# FruitBox_LED.net
KiCad netlist of a schematic drawn in Altium Designer
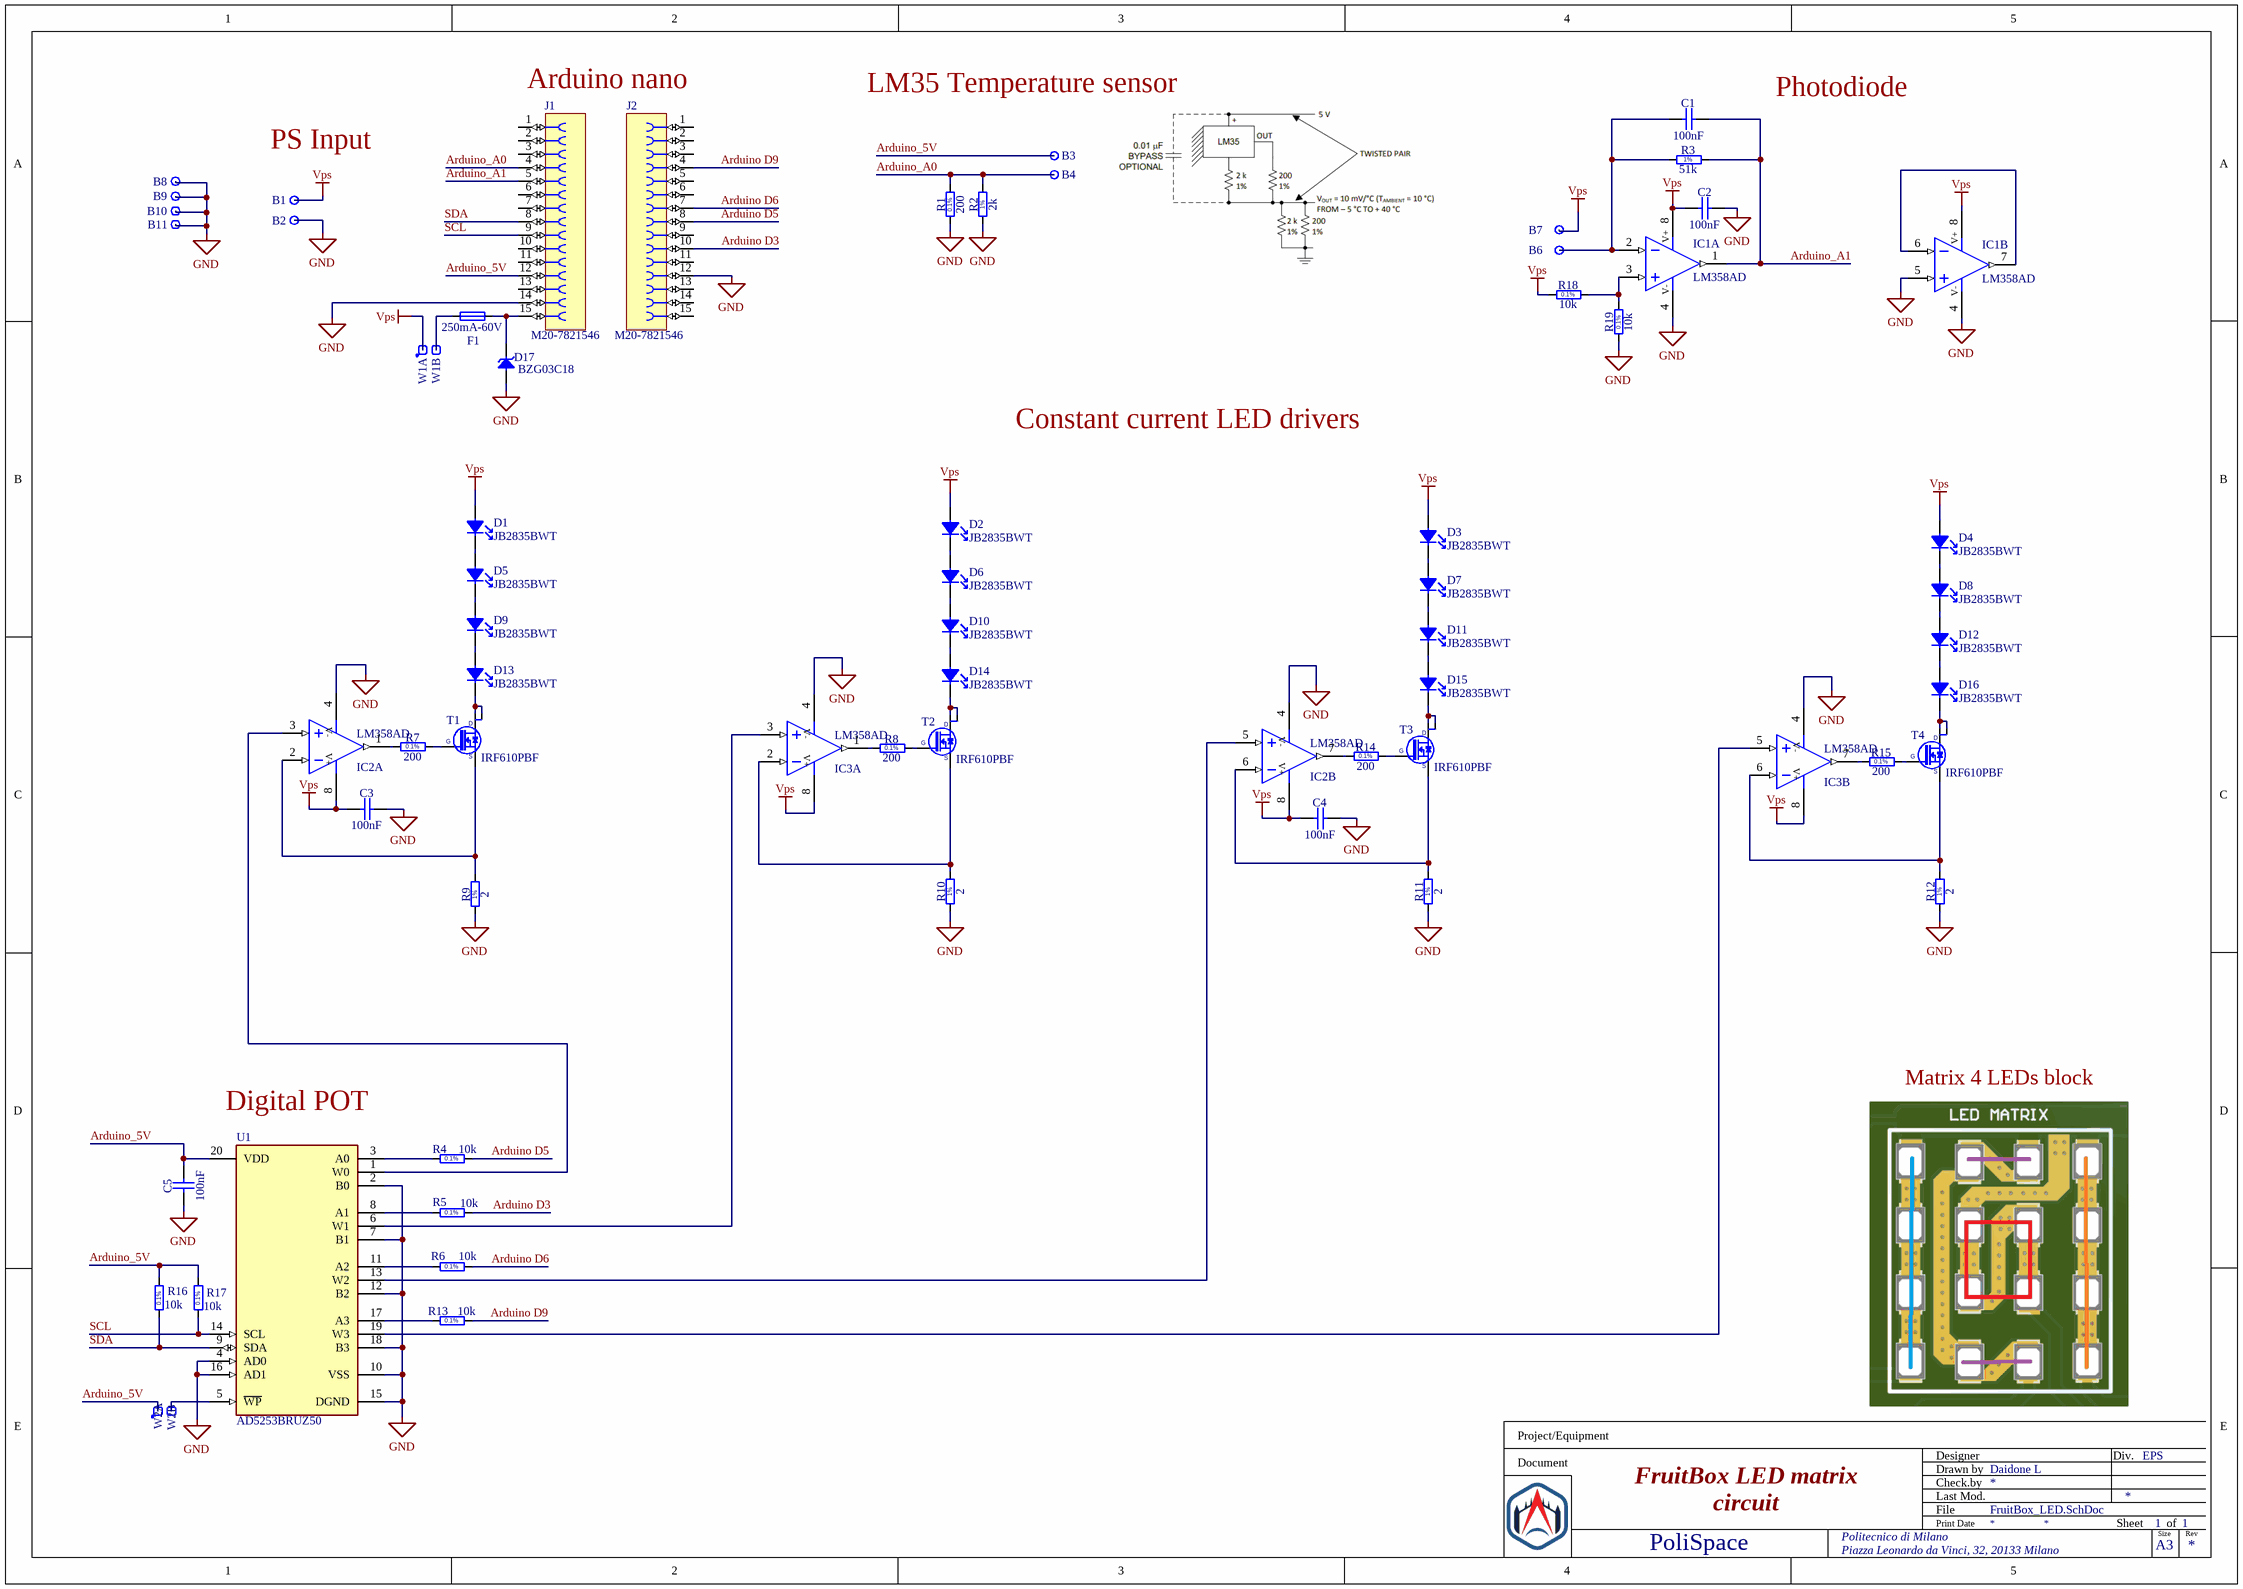
[diagram p0: FruitBox_LED.SchDoc]

(export (version "E")
  (design (tool "Eeschema 10.0.6"))
  (components
    (comp (ref "B1")
      (value "Banana")
      (footprint "CINCH_105-2202-201")
      (description "Single Terminal Socket")
      (fields
        (field (name "PART NUMBER") "CINCH_105-2202-201")
        (field (name "MANUFACTURER") "CINCH CONNECTIVITY")
        (field (name "AUTHOR") "CERN DEM MR")
      )
      (libsource (lib "Connectors") (part "Single Terminal Socket"))
    )
    (comp (ref "B2")
      (value "Banana")
      (footprint "CINCH_105-2203-201")
      (description "Single Terminal Socket")
      (fields
        (field (name "PART NUMBER") "CINCH_105-2203-201")
        (field (name "MANUFACTURER") "CINCH CONNECTIVITY")
        (field (name "AUTHOR") "CERN DEM MR")
      )
      (libsource (lib "Connectors") (part "Single Terminal Socket"))
    )
    (comp (ref "B3")
      (value "Plated Hole")
      (footprint "c130h80")
      (description "Single Terminal Socket")
      (fields (field (name "PART NUMBER") "PLATED_HOLE0.8_PAD1.3") (field (name "AUTHOR") "CERN DEM JLC"))
      (libsource (lib "Eletro-mechanical") (part "Single Terminal Socket"))
    )
    (comp (ref "B4")
      (value "Plated Hole")
      (footprint "c130h80")
      (description "Single Terminal Socket")
      (fields (field (name "PART NUMBER") "PLATED_HOLE0.8_PAD1.3") (field (name "AUTHOR") "CERN DEM JLC"))
      (libsource (lib "Eletro-mechanical") (part "Single Terminal Socket"))
    )
    (comp (ref "B6")
      (value "Plated Hole")
      (footprint "c130h80")
      (description "Single Terminal Socket")
      (fields (field (name "PART NUMBER") "PLATED_HOLE0.8_PAD1.3") (field (name "AUTHOR") "CERN DEM JLC"))
      (libsource (lib "Eletro-mechanical") (part "Single Terminal Socket"))
    )
    (comp (ref "B7")
      (value "Plated Hole")
      (footprint "c130h80")
      (description "Single Terminal Socket")
      (fields (field (name "PART NUMBER") "PLATED_HOLE0.8_PAD1.3") (field (name "AUTHOR") "CERN DEM JLC"))
      (libsource (lib "Eletro-mechanical") (part "Single Terminal Socket"))
    )
    (comp (ref "B8")
      (value "Plated Hole")
      (footprint "MTG320_550")
      (description "Single Terminal Socket")
      (fields (field (name "PART NUMBER") "PLATED_HOLE3.2_PAD5.5") (field (name "AUTHOR") "CERN DEM JMW"))
      (libsource (lib "Eletro-mechanical") (part "Single Terminal Socket"))
    )
    (comp (ref "B9")
      (value "Plated Hole")
      (footprint "MTG320_550")
      (description "Single Terminal Socket")
      (fields (field (name "PART NUMBER") "PLATED_HOLE3.2_PAD5.5") (field (name "AUTHOR") "CERN DEM JMW"))
      (libsource (lib "Eletro-mechanical") (part "Single Terminal Socket"))
    )
    (comp (ref "B10")
      (value "Plated Hole")
      (footprint "MTG320_550")
      (description "Single Terminal Socket")
      (fields (field (name "PART NUMBER") "PLATED_HOLE3.2_PAD5.5") (field (name "AUTHOR") "CERN DEM JMW"))
      (libsource (lib "Eletro-mechanical") (part "Single Terminal Socket"))
    )
    (comp (ref "B11")
      (value "Plated Hole")
      (footprint "MTG320_550")
      (description "Single Terminal Socket")
      (fields (field (name "PART NUMBER") "PLATED_HOLE3.2_PAD5.5") (field (name "AUTHOR") "CERN DEM JMW"))
      (libsource (lib "Eletro-mechanical") (part "Single Terminal Socket"))
    )
    (comp (ref "C1")
      (value "100nF")
      (footprint "CAPC1608X87N")
      (description "Non-polarised capacitor")
      (fields
        (field (name "PART NUMBER") "CC0603_100NF_50V_10%_X7R")
        (field (name "VOLTAGE") "50V")
        (field (name "AUTHOR") "CERN DEM JLC")
      )
      (libsource (lib "Capacitors") (part "Capacitor - non polarized"))
    )
    (comp (ref "C2")
      (value "100nF")
      (footprint "CAPC1608X87N")
      (description "Non-polarised capacitor")
      (fields
        (field (name "PART NUMBER") "CC0603_100NF_50V_10%_X7R")
        (field (name "VOLTAGE") "50V")
        (field (name "AUTHOR") "CERN DEM JLC")
      )
      (libsource (lib "Capacitors") (part "Capacitor - non polarized"))
    )
    (comp (ref "C3")
      (value "100nF")
      (footprint "CAPC1608X87N")
      (description "Non-polarised capacitor")
      (fields
        (field (name "PART NUMBER") "CC0603_100NF_50V_10%_X7R")
        (field (name "VOLTAGE") "50V")
        (field (name "AUTHOR") "CERN DEM JLC")
      )
      (libsource (lib "Capacitors") (part "Capacitor - non polarized"))
    )
    (comp (ref "C4")
      (value "100nF")
      (footprint "CAPC1608X87N")
      (description "Non-polarised capacitor")
      (fields
        (field (name "PART NUMBER") "CC0603_100NF_50V_10%_X7R")
        (field (name "VOLTAGE") "50V")
        (field (name "AUTHOR") "CERN DEM JLC")
      )
      (libsource (lib "Capacitors") (part "Capacitor - non polarized"))
    )
    (comp (ref "C5")
      (value "100nF")
      (footprint "CAPC1608X87N")
      (description "Non-polarised capacitor")
      (fields
        (field (name "PART NUMBER") "CC0603_100NF_50V_10%_X7R")
        (field (name "VOLTAGE") "50V")
        (field (name "AUTHOR") "CERN DEM JLC")
      )
      (libsource (lib "Capacitors") (part "Capacitor - non polarized"))
    )
    (comp (ref "D1")
      (value "JB2835BWT")
      (footprint "JB2835BWT")
      (libsource (lib "6SCubeSat") (part "JB2835BWT-G-U35GA0000"))
    )
    (comp (ref "D2")
      (value "JB2835BWT")
      (footprint "JB2835BWT")
      (libsource (lib "6SCubeSat") (part "JB2835BWT-G-U35GA0000"))
    )
    (comp (ref "D3")
      (value "JB2835BWT")
      (footprint "JB2835BWT")
      (libsource (lib "6SCubeSat") (part "JB2835BWT-G-U35GA0000"))
    )
    (comp (ref "D4")
      (value "JB2835BWT")
      (footprint "JB2835BWT")
      (libsource (lib "6SCubeSat") (part "JB2835BWT-G-U35GA0000"))
    )
    (comp (ref "D5")
      (value "JB2835BWT")
      (footprint "JB2835BWT")
      (libsource (lib "6SCubeSat") (part "JB2835BWT-G-U35GA0000"))
    )
    (comp (ref "D6")
      (value "JB2835BWT")
      (footprint "JB2835BWT")
      (libsource (lib "6SCubeSat") (part "JB2835BWT-G-U35GA0000"))
    )
    (comp (ref "D7")
      (value "JB2835BWT")
      (footprint "JB2835BWT")
      (libsource (lib "6SCubeSat") (part "JB2835BWT-G-U35GA0000"))
    )
    (comp (ref "D8")
      (value "JB2835BWT")
      (footprint "JB2835BWT")
      (libsource (lib "6SCubeSat") (part "JB2835BWT-G-U35GA0000"))
    )
    (comp (ref "D9")
      (value "JB2835BWT")
      (footprint "JB2835BWT")
      (libsource (lib "6SCubeSat") (part "JB2835BWT-G-U35GA0000"))
    )
    (comp (ref "D10")
      (value "JB2835BWT")
      (footprint "JB2835BWT")
      (libsource (lib "6SCubeSat") (part "JB2835BWT-G-U35GA0000"))
    )
    (comp (ref "D11")
      (value "JB2835BWT")
      (footprint "JB2835BWT")
      (libsource (lib "6SCubeSat") (part "JB2835BWT-G-U35GA0000"))
    )
    (comp (ref "D12")
      (value "JB2835BWT")
      (footprint "JB2835BWT")
      (libsource (lib "6SCubeSat") (part "JB2835BWT-G-U35GA0000"))
    )
    (comp (ref "D13")
      (value "JB2835BWT")
      (footprint "JB2835BWT")
      (libsource (lib "6SCubeSat") (part "JB2835BWT-G-U35GA0000"))
    )
    (comp (ref "D14")
      (value "JB2835BWT")
      (footprint "JB2835BWT")
      (libsource (lib "6SCubeSat") (part "JB2835BWT-G-U35GA0000"))
    )
    (comp (ref "D15")
      (value "JB2835BWT")
      (footprint "JB2835BWT")
      (libsource (lib "6SCubeSat") (part "JB2835BWT-G-U35GA0000"))
    )
    (comp (ref "D16")
      (value "JB2835BWT")
      (footprint "JB2835BWT")
      (libsource (lib "6SCubeSat") (part "JB2835BWT-G-U35GA0000"))
    )
    (comp (ref "D17")
      (value "BZG03C18")
      (footprint "DIOM5326X230N")
      (description "Zener Diode")
      (fields
        (field (name "VOLTAGE") "18V")
        (field (name "POWER") "1.25W")
        (field (name "AUTHOR") "CERN DEM JLC")
      )
      (libsource (lib "ICs And Semiconductors") (part "Diode Zener"))
    )
    (comp (ref "F1")
      (value "250mA-60V")
      (footprint "FUSR_BEL_0ZCJ0010FF2E")
      (description "Fuse")
      (fields
        (field (name "PART NUMBER") "FUSR1206_BEL_0ZCJ0010FF2E")
        (field (name "MANUFACTURER") "BEL")
        (field (name "AUTHOR") "CERN DEM BR")
      )
      (libsource (lib "Eletro-mechanical") (part "Fuse"))
    )
    (comp (ref "IC1")
      (value "LM358AD")
      (footprint "SOIC127P600X175-8N")
      (description "Dual Operational Amplifier")
      (fields (field (name "MANUFACTURER") "TEXAS INSTRUMENTS") (field (name "AUTHOR") "CERN DEM JLC"))
      (libsource (lib "ICs And Semiconductors") (part "Operational Amplifier x2 Type1"))
    )
    (comp (ref "IC2")
      (value "LM358AD")
      (footprint "SOIC127P600X175-8N")
      (description "Dual Operational Amplifier")
      (fields (field (name "MANUFACTURER") "TEXAS INSTRUMENTS") (field (name "AUTHOR") "CERN DEM JLC"))
      (libsource (lib "ICs And Semiconductors") (part "Operational Amplifier x2 Type1"))
    )
    (comp (ref "IC3")
      (value "LM358AD")
      (footprint "SOIC127P600X175-8N")
      (description "Dual Operational Amplifier")
      (fields (field (name "MANUFACTURER") "TEXAS INSTRUMENTS") (field (name "AUTHOR") "CERN DEM JLC"))
      (libsource (lib "ICs And Semiconductors") (part "Operational Amplifier x2 Type1"))
    )
    (comp (ref "J1")
      (value "M20-7821546")
      (footprint "M20-7821546")
      (libsource (lib "6SCubeSat") (part "M20-7821546"))
    )
    (comp (ref "J2")
      (value "M20-7821546")
      (footprint "M20-7821546")
      (libsource (lib "") (part "M20-7821546_1"))
    )
    (comp (ref "R1")
      (value "200")
      (footprint "RESC1608X64N")
      (description "Resistor - 0.1%")
      (fields
        (field (name "PART NUMBER") "R0603_200R_0.1%_0.1W_25PPM")
        (field (name "POWER") "0.1W")
        (field (name "AUTHOR") "CERN DEM JLC")
      )
      (libsource (lib "Resistors") (part "Resistor - 0.1%"))
    )
    (comp (ref "R2")
      (value "2k")
      (footprint "RESC1608X55N")
      (description "Resistor - 1%")
      (fields
        (field (name "PART NUMBER") "R0603_2K_1%_0.1W_100PPM")
        (field (name "POWER") "0.1W")
        (field (name "AUTHOR") "CERN DEM JLC")
      )
      (libsource (lib "Resistors") (part "Resistor - 1%"))
    )
    (comp (ref "R3")
      (value "51k")
      (footprint "RESC2012X60N")
      (description "Resistor - 1%")
      (fields
        (field (name "PART NUMBER") "R0805_51K_1%_0.125W_100PPM")
        (field (name "POWER") "0.125W")
        (field (name "AUTHOR") "CERN DEM JLC")
      )
      (libsource (lib "Resistors") (part "Resistor - 1%"))
    )
    (comp (ref "R4")
      (value "10k")
      (footprint "RESC1608X64N")
      (description "Resistor - 0.1%")
      (fields
        (field (name "PART NUMBER") "R0603_10K_0.1%_0.1W_25PPM")
        (field (name "POWER") "0.1W")
        (field (name "AUTHOR") "CERN DEM JMW")
      )
      (libsource (lib "Resistors") (part "Resistor - 0.1%"))
    )
    (comp (ref "R5")
      (value "10k")
      (footprint "RESC1608X64N")
      (description "Resistor - 0.1%")
      (fields
        (field (name "PART NUMBER") "R0603_10K_0.1%_0.1W_25PPM")
        (field (name "POWER") "0.1W")
        (field (name "AUTHOR") "CERN DEM JMW")
      )
      (libsource (lib "Resistors") (part "Resistor - 0.1%"))
    )
    (comp (ref "R6")
      (value "10k")
      (footprint "RESC1608X64N")
      (description "Resistor - 0.1%")
      (fields
        (field (name "PART NUMBER") "R0603_10K_0.1%_0.1W_25PPM")
        (field (name "POWER") "0.1W")
        (field (name "AUTHOR") "CERN DEM JMW")
      )
      (libsource (lib "Resistors") (part "Resistor - 0.1%"))
    )
    (comp (ref "R7")
      (value "200")
      (footprint "RESC1608X64N")
      (description "Resistor - 0.1%")
      (fields
        (field (name "PART NUMBER") "R0603_200R_0.1%_0.1W_25PPM")
        (field (name "POWER") "0.1W")
        (field (name "AUTHOR") "CERN DEM JLC")
      )
      (libsource (lib "Resistors") (part "Resistor - 0.1%"))
    )
    (comp (ref "R8")
      (value "200")
      (footprint "RESC1608X64N")
      (description "Resistor - 0.1%")
      (fields
        (field (name "PART NUMBER") "R0603_200R_0.1%_0.1W_25PPM")
        (field (name "POWER") "0.1W")
        (field (name "AUTHOR") "CERN DEM JLC")
      )
      (libsource (lib "Resistors") (part "Resistor - 0.1%"))
    )
    (comp (ref "R9")
      (value "2")
      (footprint "RES1016-630X250")
      (description "Resistor - 1%")
      (fields
        (field (name "PART NUMBER") "RMF_2R_1%_0.6W_50PPM_1016-630X250")
        (field (name "POWER") "0.6W")
        (field (name "AUTHOR") "CERN DEM JLC")
      )
      (libsource (lib "Resistors") (part "Resistor - 1%"))
    )
    (comp (ref "R10")
      (value "2")
      (footprint "RES1016-630X250")
      (description "Resistor - 1%")
      (fields
        (field (name "PART NUMBER") "RMF_2R_1%_0.6W_50PPM_1016-630X250")
        (field (name "POWER") "0.6W")
        (field (name "AUTHOR") "CERN DEM JLC")
      )
      (libsource (lib "Resistors") (part "Resistor - 1%"))
    )
    (comp (ref "R11")
      (value "2")
      (footprint "RES1016-630X250")
      (description "Resistor - 1%")
      (fields
        (field (name "PART NUMBER") "RMF_2R_1%_0.6W_50PPM_1016-630X250")
        (field (name "POWER") "0.6W")
        (field (name "AUTHOR") "CERN DEM JLC")
      )
      (libsource (lib "Resistors") (part "Resistor - 1%"))
    )
    (comp (ref "R12")
      (value "2")
      (footprint "RES1016-630X250")
      (description "Resistor - 1%")
      (fields
        (field (name "PART NUMBER") "RMF_2R_1%_0.6W_50PPM_1016-630X250")
        (field (name "POWER") "0.6W")
        (field (name "AUTHOR") "CERN DEM JLC")
      )
      (libsource (lib "Resistors") (part "Resistor - 1%"))
    )
    (comp (ref "R13")
      (value "10k")
      (footprint "RESC1608X64N")
      (description "Resistor - 0.1%")
      (fields
        (field (name "PART NUMBER") "R0603_10K_0.1%_0.1W_25PPM")
        (field (name "POWER") "0.1W")
        (field (name "AUTHOR") "CERN DEM JMW")
      )
      (libsource (lib "Resistors") (part "Resistor - 0.1%"))
    )
    (comp (ref "R14")
      (value "200")
      (footprint "RESC1608X64N")
      (description "Resistor - 0.1%")
      (fields
        (field (name "PART NUMBER") "R0603_200R_0.1%_0.1W_25PPM")
        (field (name "POWER") "0.1W")
        (field (name "AUTHOR") "CERN DEM JLC")
      )
      (libsource (lib "Resistors") (part "Resistor - 0.1%"))
    )
    (comp (ref "R15")
      (value "200")
      (footprint "RESC1608X64N")
      (description "Resistor - 0.1%")
      (fields
        (field (name "PART NUMBER") "R0603_200R_0.1%_0.1W_25PPM")
        (field (name "POWER") "0.1W")
        (field (name "AUTHOR") "CERN DEM JLC")
      )
      (libsource (lib "Resistors") (part "Resistor - 0.1%"))
    )
    (comp (ref "R16")
      (value "10k")
      (footprint "RESC1608X64N")
      (description "Resistor - 0.1%")
      (fields
        (field (name "PART NUMBER") "R0603_10K_0.1%_0.1W_25PPM")
        (field (name "POWER") "0.1W")
        (field (name "AUTHOR") "CERN DEM JMW")
      )
      (libsource (lib "Resistors") (part "Resistor - 0.1%"))
    )
    (comp (ref "R17")
      (value "10k")
      (footprint "RESC1608X64N")
      (description "Resistor - 0.1%")
      (fields
        (field (name "PART NUMBER") "R0603_10K_0.1%_0.1W_25PPM")
        (field (name "POWER") "0.1W")
        (field (name "AUTHOR") "CERN DEM JMW")
      )
      (libsource (lib "Resistors") (part "Resistor - 0.1%"))
    )
    (comp (ref "R18")
      (value "10k")
      (footprint "RESC1608X64N")
      (description "Resistor - 0.1%")
      (fields
        (field (name "PART NUMBER") "R0603_10K_0.1%_0.1W_25PPM")
        (field (name "POWER") "0.1W")
        (field (name "AUTHOR") "CERN DEM JMW")
      )
      (libsource (lib "Resistors") (part "Resistor - 0.1%"))
    )
    (comp (ref "R19")
      (value "10k")
      (footprint "RESC1608X64N")
      (description "Resistor - 0.1%")
      (fields
        (field (name "PART NUMBER") "R0603_10K_0.1%_0.1W_25PPM")
        (field (name "POWER") "0.1W")
        (field (name "AUTHOR") "CERN DEM JMW")
      )
      (libsource (lib "Resistors") (part "Resistor - 0.1%"))
    )
    (comp (ref "T1")
      (value "IRF610PBF")
      (footprint "TO-220-H")
      (description "N-CHANNEL MOSFET WITH DIODE AND 2 DRAIN")
      (fields
        (field (name "PART NUMBER") "IRF610PBF_h")
        (field (name "MANUFACTURER") "VISHAY SILICONIX")
        (field (name "AUTHOR") "CERN DEM JLC")
      )
      (libsource (lib "ICs And Semiconductors") (part "N-MOSFET-D 1G 2D 3S 4D"))
    )
    (comp (ref "T2")
      (value "IRF610PBF")
      (footprint "TO-220-H")
      (description "N-CHANNEL MOSFET WITH DIODE AND 2 DRAIN")
      (fields
        (field (name "PART NUMBER") "IRF610PBF_h")
        (field (name "MANUFACTURER") "VISHAY SILICONIX")
        (field (name "AUTHOR") "CERN DEM JLC")
      )
      (libsource (lib "ICs And Semiconductors") (part "N-MOSFET-D 1G 2D 3S 4D"))
    )
    (comp (ref "T3")
      (value "IRF610PBF")
      (footprint "TO-220-H")
      (description "N-CHANNEL MOSFET WITH DIODE AND 2 DRAIN")
      (fields
        (field (name "PART NUMBER") "IRF610PBF_h")
        (field (name "MANUFACTURER") "VISHAY SILICONIX")
        (field (name "AUTHOR") "CERN DEM JLC")
      )
      (libsource (lib "ICs And Semiconductors") (part "N-MOSFET-D 1G 2D 3S 4D"))
    )
    (comp (ref "T4")
      (value "IRF610PBF")
      (footprint "TO-220-H")
      (description "N-CHANNEL MOSFET WITH DIODE AND 2 DRAIN")
      (fields
        (field (name "PART NUMBER") "IRF610PBF_h")
        (field (name "MANUFACTURER") "VISHAY SILICONIX")
        (field (name "AUTHOR") "CERN DEM JLC")
      )
      (libsource (lib "ICs And Semiconductors") (part "N-MOSFET-D 1G 2D 3S 4D"))
    )
    (comp (ref "U1")
      (value "AD5253BRUZ50")
      (footprint "FP-RU-20-IPC_C")
      (description "IC DGTL POT 50KOHM 64TAP 20TSSOP")
      (fields (field (name "TOLERANCE") "20%"))
      (libsource (lib "Altium Content Vault") (part "99a24b26ea6d6ce59f51e99b3587243"))
    )
    (comp (ref "W1")
      (value "Header 2")
      (footprint "HARWIN_M20-9990246")
      (description "2 Mini Wire-Wrap Contact Strip Header")
      (fields
        (field (name "PART NUMBER") "HARWIN_M20-9990246")
        (field (name "MANUFACTURER") "HARWIN")
        (field (name "AUTHOR") "CERN DEM JLC")
      )
      (libsource (lib "Connectors") (part "Wire-Wrap Contact x2"))
    )
    (comp (ref "W2")
      (value "Header 2")
      (footprint "HARWIN_M20-9990246")
      (description "2 Mini Wire-Wrap Contact Strip Header")
      (fields
        (field (name "PART NUMBER") "HARWIN_M20-9990246")
        (field (name "MANUFACTURER") "HARWIN")
        (field (name "AUTHOR") "CERN DEM JLC")
      )
      (libsource (lib "Connectors") (part "Wire-Wrap Contact x2"))
    )
  )
  (nets
    (net (code "1") (name "/Arduino D3") (class "Default")
      (node (ref "J2") (pin "10") (pinfunction "10_10") (pintype "bidirectional"))
      (node (ref "R5") (pin "1") (pinfunction "1_1") (pintype "passive"))
    )
    (net (code "2") (name "/Arduino D5") (class "Default")
      (node (ref "J2") (pin "8") (pinfunction "8_8") (pintype "bidirectional"))
      (node (ref "R4") (pin "1") (pinfunction "1_1") (pintype "passive"))
    )
    (net (code "3") (name "/Arduino D6") (class "Default")
      (node (ref "J2") (pin "7") (pinfunction "7_7") (pintype "bidirectional"))
      (node (ref "R6") (pin "1") (pinfunction "1_1") (pintype "passive"))
    )
    (net (code "4") (name "/Arduino D9") (class "Default")
      (node (ref "J2") (pin "4") (pinfunction "4_4") (pintype "bidirectional"))
      (node (ref "R13") (pin "1") (pinfunction "1_1") (pintype "passive"))
    )
    (net (code "5") (name "/Arduino_5V") (class "Default")
      (node (ref "B3") (pin "1") (pinfunction "1_1") (pintype "bidirectional"))
      (node (ref "C5") (pin "1") (pinfunction "1_1") (pintype "passive"))
      (node (ref "J1") (pin "12") (pinfunction "12_12") (pintype "bidirectional"))
      (node (ref "R16") (pin "2") (pinfunction "2_2") (pintype "passive"))
      (node (ref "R17") (pin "2") (pinfunction "2_2") (pintype "passive"))
      (node (ref "U1") (pin "20") (pinfunction "VDD_20") (pintype "power_in"))
      (node (ref "W2") (pin "1") (pinfunction "1_1") (pintype "bidirectional"))
    )
    (net (code "6") (name "/Arduino_A0") (class "Default")
      (node (ref "B4") (pin "1") (pinfunction "1_1") (pintype "bidirectional"))
      (node (ref "J1") (pin "4") (pinfunction "4_4") (pintype "bidirectional"))
      (node (ref "R1") (pin "2") (pinfunction "2_2") (pintype "passive"))
      (node (ref "R2") (pin "2") (pinfunction "2_2") (pintype "passive"))
    )
    (net (code "7") (name "/Arduino_A1") (class "Default")
      (node (ref "C1") (pin "2") (pinfunction "2_2") (pintype "passive"))
      (node (ref "IC1") (pin "1") (pinfunction "OUT_1") (pintype "output"))
      (node (ref "J1") (pin "5") (pinfunction "5_5") (pintype "bidirectional"))
      (node (ref "R3") (pin "2") (pinfunction "2_2") (pintype "passive"))
    )
    (net (code "8") (name "/SCL") (class "Default")
      (node (ref "J1") (pin "9") (pinfunction "9_9") (pintype "bidirectional"))
      (node (ref "R17") (pin "1") (pinfunction "1_1") (pintype "passive"))
      (node (ref "U1") (pin "14") (pinfunction "SCL_14") (pintype "input"))
    )
    (net (code "9") (name "/SDA") (class "Default")
      (node (ref "J1") (pin "8") (pinfunction "8_8") (pintype "bidirectional"))
      (node (ref "R16") (pin "1") (pinfunction "1_1") (pintype "passive"))
      (node (ref "U1") (pin "9") (pinfunction "SDA_9") (pintype "bidirectional"))
    )
    (net (code "10") (name "GND") (class "Default")
      (node (ref "B10") (pin "1") (pinfunction "1_1") (pintype "bidirectional"))
      (node (ref "B11") (pin "1") (pinfunction "1_1") (pintype "bidirectional"))
      (node (ref "B2") (pin "1") (pinfunction "1_1") (pintype "bidirectional"))
      (node (ref "B8") (pin "1") (pinfunction "1_1") (pintype "bidirectional"))
      (node (ref "B9") (pin "1") (pinfunction "1_1") (pintype "bidirectional"))
      (node (ref "C2") (pin "2") (pinfunction "2_2") (pintype "passive"))
      (node (ref "C3") (pin "2") (pinfunction "2_2") (pintype "passive"))
      (node (ref "C4") (pin "2") (pinfunction "2_2") (pintype "passive"))
      (node (ref "C5") (pin "2") (pinfunction "2_2") (pintype "passive"))
      (node (ref "D17") (pin "2") (pinfunction "A_2") (pintype "passive"))
      (node (ref "IC1") (pin "4") (pinfunction "V-_4") (pintype "power_in"))
      (node (ref "IC1") (pin "5") (pinfunction "IN+_5") (pintype "input"))
      (node (ref "IC2") (pin "4") (pinfunction "V-_4") (pintype "power_in"))
      (node (ref "IC3") (pin "4") (pinfunction "V-_4") (pintype "power_in"))
      (node (ref "J1") (pin "14") (pinfunction "14_14") (pintype "bidirectional"))
      (node (ref "J2") (pin "12") (pinfunction "12_12") (pintype "bidirectional"))
      (node (ref "R1") (pin "1") (pinfunction "1_1") (pintype "passive"))
      (node (ref "R10") (pin "1") (pinfunction "1_1") (pintype "passive"))
      (node (ref "R11") (pin "1") (pinfunction "1_1") (pintype "passive"))
      (node (ref "R12") (pin "1") (pinfunction "1_1") (pintype "passive"))
      (node (ref "R19") (pin "1") (pinfunction "1_1") (pintype "passive"))
      (node (ref "R2") (pin "1") (pinfunction "1_1") (pintype "passive"))
      (node (ref "R9") (pin "1") (pinfunction "1_1") (pintype "passive"))
      (node (ref "U1") (pin "10") (pinfunction "VSS_10") (pintype "power_in"))
      (node (ref "U1") (pin "12") (pinfunction "B2_12") (pintype "passive"))
      (node (ref "U1") (pin "15") (pinfunction "DGND_15") (pintype "power_in"))
      (node (ref "U1") (pin "16") (pinfunction "AD1_16") (pintype "input"))
      (node (ref "U1") (pin "18") (pinfunction "B3_18") (pintype "passive"))
      (node (ref "U1") (pin "2") (pinfunction "B0_2") (pintype "passive"))
      (node (ref "U1") (pin "4") (pinfunction "AD0_4") (pintype "input"))
      (node (ref "U1") (pin "7") (pinfunction "B1_7") (pintype "passive"))
    )
    (net (code "11") (name "Net-(D1-C)") (class "Default")
      (node (ref "D1") (pin "1") (pinfunction "C_1") (pintype "passive"))
      (node (ref "D5") (pin "2") (pinfunction "A_2") (pintype "passive"))
    )
    (net (code "12") (name "Net-(D2-C)") (class "Default")
      (node (ref "D2") (pin "1") (pinfunction "C_1") (pintype "passive"))
      (node (ref "D6") (pin "2") (pinfunction "A_2") (pintype "passive"))
    )
    (net (code "13") (name "Net-(D3-C)") (class "Default")
      (node (ref "D3") (pin "1") (pinfunction "C_1") (pintype "passive"))
      (node (ref "D7") (pin "2") (pinfunction "A_2") (pintype "passive"))
    )
    (net (code "14") (name "Net-(D4-C)") (class "Default")
      (node (ref "D4") (pin "1") (pinfunction "C_1") (pintype "passive"))
      (node (ref "D8") (pin "2") (pinfunction "A_2") (pintype "passive"))
    )
    (net (code "15") (name "Net-(D5-C)") (class "Default")
      (node (ref "D5") (pin "1") (pinfunction "C_1") (pintype "passive"))
      (node (ref "D9") (pin "2") (pinfunction "A_2") (pintype "passive"))
    )
    (net (code "16") (name "Net-(D10-A)") (class "Default")
      (node (ref "D10") (pin "2") (pinfunction "A_2") (pintype "passive"))
      (node (ref "D6") (pin "1") (pinfunction "C_1") (pintype "passive"))
    )
    (net (code "17") (name "Net-(D10-C)") (class "Default")
      (node (ref "D10") (pin "1") (pinfunction "C_1") (pintype "passive"))
      (node (ref "D14") (pin "2") (pinfunction "A_2") (pintype "passive"))
    )
    (net (code "18") (name "Net-(D11-A)") (class "Default")
      (node (ref "D11") (pin "2") (pinfunction "A_2") (pintype "passive"))
      (node (ref "D7") (pin "1") (pinfunction "C_1") (pintype "passive"))
    )
    (net (code "19") (name "Net-(D11-C)") (class "Default")
      (node (ref "D11") (pin "1") (pinfunction "C_1") (pintype "passive"))
      (node (ref "D15") (pin "2") (pinfunction "A_2") (pintype "passive"))
    )
    (net (code "20") (name "Net-(D12-A)") (class "Default")
      (node (ref "D12") (pin "2") (pinfunction "A_2") (pintype "passive"))
      (node (ref "D8") (pin "1") (pinfunction "C_1") (pintype "passive"))
    )
    (net (code "21") (name "Net-(D12-C)") (class "Default")
      (node (ref "D12") (pin "1") (pinfunction "C_1") (pintype "passive"))
      (node (ref "D16") (pin "2") (pinfunction "A_2") (pintype "passive"))
    )
    (net (code "22") (name "Net-(D13-A)") (class "Default")
      (node (ref "D13") (pin "2") (pinfunction "A_2") (pintype "passive"))
      (node (ref "D9") (pin "1") (pinfunction "C_1") (pintype "passive"))
    )
    (net (code "23") (name "Net-(D13-C)") (class "Default")
      (node (ref "D13") (pin "1") (pinfunction "C_1") (pintype "passive"))
      (node (ref "T1") (pin "2") (pinfunction "D_2") (pintype "passive"))
      (node (ref "T1") (pin "4") (pinfunction "D_4") (pintype "passive"))
    )
    (net (code "24") (name "Net-(D14-C)") (class "Default")
      (node (ref "D14") (pin "1") (pinfunction "C_1") (pintype "passive"))
      (node (ref "T2") (pin "2") (pinfunction "D_2") (pintype "passive"))
      (node (ref "T2") (pin "4") (pinfunction "D_4") (pintype "passive"))
    )
    (net (code "25") (name "Net-(D15-C)") (class "Default")
      (node (ref "D15") (pin "1") (pinfunction "C_1") (pintype "passive"))
      (node (ref "T3") (pin "2") (pinfunction "D_2") (pintype "passive"))
      (node (ref "T3") (pin "4") (pinfunction "D_4") (pintype "passive"))
    )
    (net (code "26") (name "Net-(D16-C)") (class "Default")
      (node (ref "D16") (pin "1") (pinfunction "C_1") (pintype "passive"))
      (node (ref "T4") (pin "2") (pinfunction "D_2") (pintype "passive"))
      (node (ref "T4") (pin "4") (pinfunction "D_4") (pintype "passive"))
    )
    (net (code "27") (name "Net-(D17-C)") (class "Default")
      (node (ref "D17") (pin "1") (pinfunction "C_1") (pintype "passive"))
      (node (ref "F1") (pin "2") (pinfunction "2_2") (pintype "passive"))
      (node (ref "J1") (pin "15") (pinfunction "15_15") (pintype "bidirectional"))
    )
    (net (code "28") (name "Net-(F1-Pad1)") (class "Default")
      (node (ref "F1") (pin "1") (pinfunction "1_1") (pintype "passive"))
      (node (ref "W1") (pin "2") (pinfunction "2_2") (pintype "bidirectional"))
    )
    (net (code "29") (name "Net-(IC1A-IN+)") (class "Default")
      (node (ref "IC1") (pin "3") (pinfunction "IN+_3") (pintype "input"))
      (node (ref "R18") (pin "2") (pinfunction "2_2") (pintype "passive"))
      (node (ref "R19") (pin "2") (pinfunction "2_2") (pintype "passive"))
    )
    (net (code "30") (name "Net-(IC1A-IN-)") (class "Default")
      (node (ref "B6") (pin "1") (pinfunction "1_1") (pintype "bidirectional"))
      (node (ref "C1") (pin "1") (pinfunction "1_1") (pintype "passive"))
      (node (ref "IC1") (pin "2") (pinfunction "IN-_2") (pintype "input"))
      (node (ref "R3") (pin "1") (pinfunction "1_1") (pintype "passive"))
    )
    (net (code "31") (name "Net-(IC1B-IN-)") (class "Default")
      (node (ref "IC1") (pin "6") (pinfunction "IN-_6") (pintype "input"))
      (node (ref "IC1") (pin "7") (pinfunction "OUT_7") (pintype "output"))
    )
    (net (code "32") (name "Net-(IC2A-IN+)") (class "Default")
      (node (ref "IC2") (pin "3") (pinfunction "IN+_3") (pintype "input"))
      (node (ref "U1") (pin "1") (pinfunction "W0_1") (pintype "passive"))
    )
    (net (code "33") (name "Net-(IC2A-IN-)") (class "Default")
      (node (ref "IC2") (pin "2") (pinfunction "IN-_2") (pintype "input"))
      (node (ref "R9") (pin "2") (pinfunction "2_2") (pintype "passive"))
      (node (ref "T1") (pin "3") (pinfunction "S_3") (pintype "passive"))
    )
    (net (code "34") (name "Net-(IC2A-OUT)") (class "Default")
      (node (ref "IC2") (pin "1") (pinfunction "OUT_1") (pintype "output"))
      (node (ref "R7") (pin "1") (pinfunction "1_1") (pintype "passive"))
    )
    (net (code "35") (name "Net-(IC2B-IN+)") (class "Default")
      (node (ref "IC2") (pin "5") (pinfunction "IN+_5") (pintype "input"))
      (node (ref "U1") (pin "13") (pinfunction "W2_13") (pintype "passive"))
    )
    (net (code "36") (name "Net-(IC2B-IN-)") (class "Default")
      (node (ref "IC2") (pin "6") (pinfunction "IN-_6") (pintype "input"))
      (node (ref "R11") (pin "2") (pinfunction "2_2") (pintype "passive"))
      (node (ref "T3") (pin "3") (pinfunction "S_3") (pintype "passive"))
    )
    (net (code "37") (name "Net-(IC2B-OUT)") (class "Default")
      (node (ref "IC2") (pin "7") (pinfunction "OUT_7") (pintype "output"))
      (node (ref "R14") (pin "1") (pinfunction "1_1") (pintype "passive"))
    )
    (net (code "38") (name "Net-(IC3A-IN+)") (class "Default")
      (node (ref "IC3") (pin "3") (pinfunction "IN+_3") (pintype "input"))
      (node (ref "U1") (pin "6") (pinfunction "W1_6") (pintype "passive"))
    )
    (net (code "39") (name "Net-(IC3A-IN-)") (class "Default")
      (node (ref "IC3") (pin "2") (pinfunction "IN-_2") (pintype "input"))
      (node (ref "R10") (pin "2") (pinfunction "2_2") (pintype "passive"))
      (node (ref "T2") (pin "3") (pinfunction "S_3") (pintype "passive"))
    )
    (net (code "40") (name "Net-(IC3A-OUT)") (class "Default")
      (node (ref "IC3") (pin "1") (pinfunction "OUT_1") (pintype "output"))
      (node (ref "R8") (pin "1") (pinfunction "1_1") (pintype "passive"))
    )
    (net (code "41") (name "Net-(IC3B-IN+)") (class "Default")
      (node (ref "IC3") (pin "5") (pinfunction "IN+_5") (pintype "input"))
      (node (ref "U1") (pin "19") (pinfunction "W3_19") (pintype "passive"))
    )
    (net (code "42") (name "Net-(IC3B-IN-)") (class "Default")
      (node (ref "IC3") (pin "6") (pinfunction "IN-_6") (pintype "input"))
      (node (ref "R12") (pin "2") (pinfunction "2_2") (pintype "passive"))
      (node (ref "T4") (pin "3") (pinfunction "S_3") (pintype "passive"))
    )
    (net (code "43") (name "Net-(IC3B-OUT)") (class "Default")
      (node (ref "IC3") (pin "7") (pinfunction "OUT_7") (pintype "output"))
      (node (ref "R15") (pin "1") (pinfunction "1_1") (pintype "passive"))
    )
    (net (code "44") (name "Net-(T1-G)") (class "Default")
      (node (ref "R7") (pin "2") (pinfunction "2_2") (pintype "passive"))
      (node (ref "T1") (pin "1") (pinfunction "G_1") (pintype "passive"))
    )
    (net (code "45") (name "Net-(T2-G)") (class "Default")
      (node (ref "R8") (pin "2") (pinfunction "2_2") (pintype "passive"))
      (node (ref "T2") (pin "1") (pinfunction "G_1") (pintype "passive"))
    )
    (net (code "46") (name "Net-(T3-G)") (class "Default")
      (node (ref "R14") (pin "2") (pinfunction "2_2") (pintype "passive"))
      (node (ref "T3") (pin "1") (pinfunction "G_1") (pintype "passive"))
    )
    (net (code "47") (name "Net-(T4-G)") (class "Default")
      (node (ref "R15") (pin "2") (pinfunction "2_2") (pintype "passive"))
      (node (ref "T4") (pin "1") (pinfunction "G_1") (pintype "passive"))
    )
    (net (code "48") (name "Net-(U1-A0)") (class "Default")
      (node (ref "R4") (pin "2") (pinfunction "2_2") (pintype "passive"))
      (node (ref "U1") (pin "3") (pinfunction "A0_3") (pintype "passive"))
    )
    (net (code "49") (name "Net-(U1-A1)") (class "Default")
      (node (ref "R5") (pin "2") (pinfunction "2_2") (pintype "passive"))
      (node (ref "U1") (pin "8") (pinfunction "A1_8") (pintype "passive"))
    )
    (net (code "50") (name "Net-(U1-A2)") (class "Default")
      (node (ref "R6") (pin "2") (pinfunction "2_2") (pintype "passive"))
      (node (ref "U1") (pin "11") (pinfunction "A2_11") (pintype "passive"))
    )
    (net (code "51") (name "Net-(U1-A3)") (class "Default")
      (node (ref "R13") (pin "2") (pinfunction "2_2") (pintype "passive"))
      (node (ref "U1") (pin "17") (pinfunction "A3_17") (pintype "passive"))
    )
    (net (code "52") (name "Net-(U1-~{WP})") (class "Default")
      (node (ref "U1") (pin "5") (pinfunction "~{WP}_5") (pintype "input"))
      (node (ref "W2") (pin "2") (pinfunction "2_2") (pintype "bidirectional"))
    )
    (net (code "53") (name "Vps") (class "Default")
      (node (ref "B1") (pin "1") (pinfunction "1_1") (pintype "bidirectional"))
      (node (ref "B7") (pin "1") (pinfunction "1_1") (pintype "bidirectional"))
      (node (ref "C2") (pin "1") (pinfunction "1_1") (pintype "passive"))
      (node (ref "C3") (pin "1") (pinfunction "1_1") (pintype "passive"))
      (node (ref "C4") (pin "1") (pinfunction "1_1") (pintype "passive"))
      (node (ref "D1") (pin "2") (pinfunction "A_2") (pintype "passive"))
      (node (ref "D2") (pin "2") (pinfunction "A_2") (pintype "passive"))
      (node (ref "D3") (pin "2") (pinfunction "A_2") (pintype "passive"))
      (node (ref "D4") (pin "2") (pinfunction "A_2") (pintype "passive"))
      (node (ref "IC1") (pin "8") (pinfunction "V+_8") (pintype "power_in"))
      (node (ref "IC2") (pin "8") (pinfunction "V+_8") (pintype "power_in"))
      (node (ref "IC3") (pin "8") (pinfunction "V+_8") (pintype "power_in"))
      (node (ref "R18") (pin "1") (pinfunction "1_1") (pintype "passive"))
      (node (ref "W1") (pin "1") (pinfunction "1_1") (pintype "bidirectional"))
    )
    (net (code "54") (name "unconnected-(J1-Pad1)") (class "Default")
      (node (ref "J1") (pin "1") (pinfunction "1_1") (pintype "bidirectional"))
    )
    (net (code "55") (name "unconnected-(J1-Pad2)") (class "Default")
      (node (ref "J1") (pin "2") (pinfunction "2_2") (pintype "bidirectional"))
    )
    (net (code "56") (name "unconnected-(J1-Pad3)") (class "Default")
      (node (ref "J1") (pin "3") (pinfunction "3_3") (pintype "bidirectional"))
    )
    (net (code "57") (name "unconnected-(J1-Pad6)") (class "Default")
      (node (ref "J1") (pin "6") (pinfunction "6_6") (pintype "bidirectional"))
    )
    (net (code "58") (name "unconnected-(J1-Pad7)") (class "Default")
      (node (ref "J1") (pin "7") (pinfunction "7_7") (pintype "bidirectional"))
    )
    (net (code "59") (name "unconnected-(J1-Pad10)") (class "Default")
      (node (ref "J1") (pin "10") (pinfunction "10_10") (pintype "bidirectional"))
    )
    (net (code "60") (name "unconnected-(J1-Pad11)") (class "Default")
      (node (ref "J1") (pin "11") (pinfunction "11_11") (pintype "bidirectional"))
    )
    (net (code "61") (name "unconnected-(J1-Pad13)") (class "Default")
      (node (ref "J1") (pin "13") (pinfunction "13_13") (pintype "bidirectional"))
    )
    (net (code "62") (name "unconnected-(J2-Pad1)") (class "Default")
      (node (ref "J2") (pin "1") (pinfunction "1_1") (pintype "bidirectional"))
    )
    (net (code "63") (name "unconnected-(J2-Pad2)") (class "Default")
      (node (ref "J2") (pin "2") (pinfunction "2_2") (pintype "bidirectional"))
    )
    (net (code "64") (name "unconnected-(J2-Pad3)") (class "Default")
      (node (ref "J2") (pin "3") (pinfunction "3_3") (pintype "bidirectional"))
    )
    (net (code "65") (name "unconnected-(J2-Pad5)") (class "Default")
      (node (ref "J2") (pin "5") (pinfunction "5_5") (pintype "bidirectional"))
    )
    (net (code "66") (name "unconnected-(J2-Pad6)") (class "Default")
      (node (ref "J2") (pin "6") (pinfunction "6_6") (pintype "bidirectional"))
    )
    (net (code "67") (name "unconnected-(J2-Pad9)") (class "Default")
      (node (ref "J2") (pin "9") (pinfunction "9_9") (pintype "bidirectional"))
    )
    (net (code "68") (name "unconnected-(J2-Pad11)") (class "Default")
      (node (ref "J2") (pin "11") (pinfunction "11_11") (pintype "bidirectional"))
    )
    (net (code "69") (name "unconnected-(J2-Pad13)") (class "Default")
      (node (ref "J2") (pin "13") (pinfunction "13_13") (pintype "bidirectional"))
    )
    (net (code "70") (name "unconnected-(J2-Pad14)") (class "Default")
      (node (ref "J2") (pin "14") (pinfunction "14_14") (pintype "bidirectional"))
    )
    (net (code "71") (name "unconnected-(J2-Pad15)") (class "Default")
      (node (ref "J2") (pin "15") (pinfunction "15_15") (pintype "bidirectional"))
    )
  )
)
